# PickupBoard.net
KiCad netlist of a schematic drawn in EAGLE
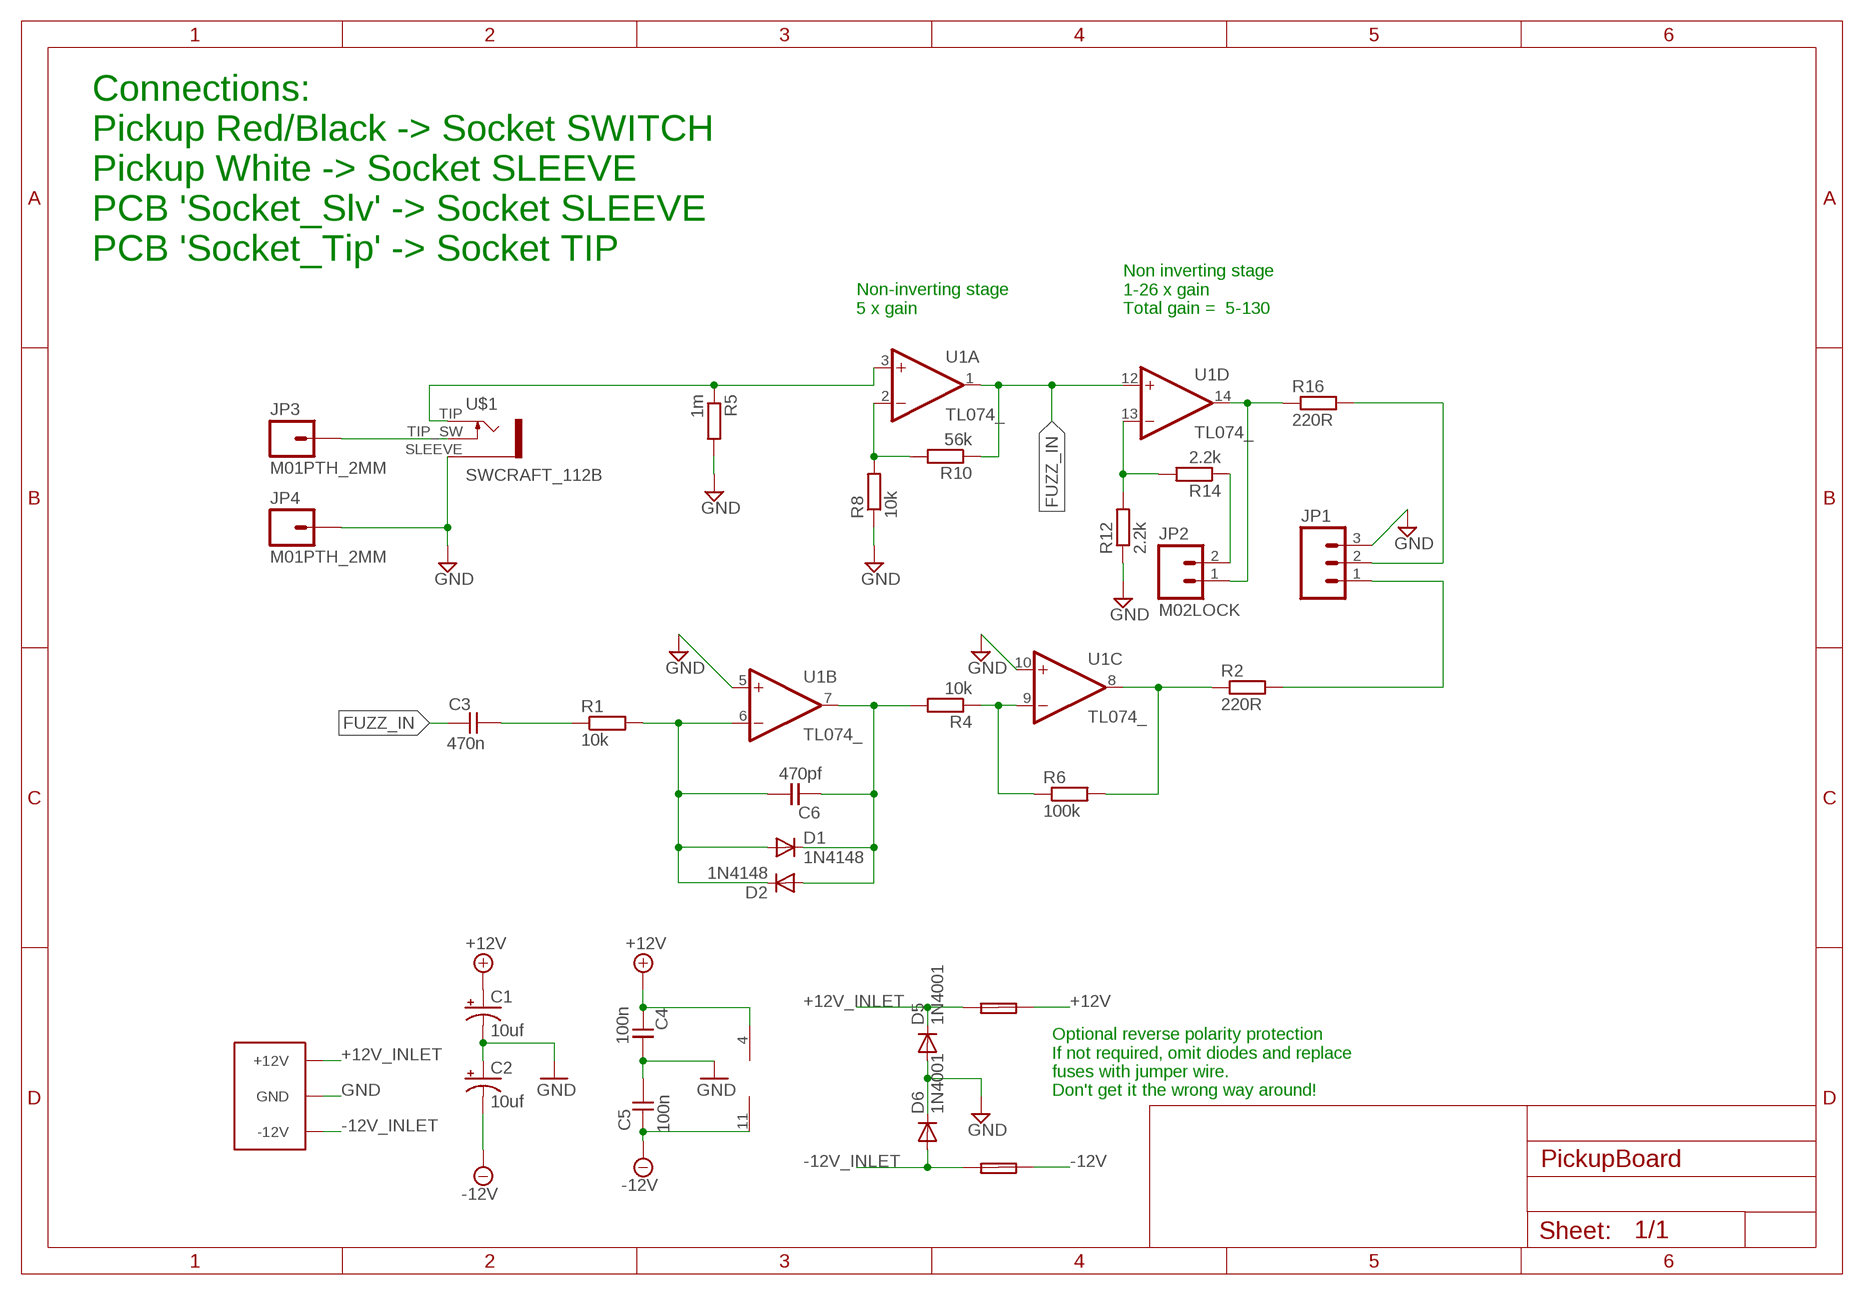
[diagram p0: schematic, sheet 1]

(export (version "E")
  (design (tool "Eeschema 10.0.6"))
  (components
    (comp (ref "1")
      (value "FUSE")
      (footprint "eagle-import:C050H075X075")
      (libsource (lib "eagle-import") (part "PTC_FUSEPOLY_FUSE"))
    )
    (comp (ref "C1")
      (value "10uf")
      (footprint "eagle-import:CPOL-RADIAL-10UF-25V")
      (libsource (lib "eagle-import") (part "CAP_POLPTH2"))
    )
    (comp (ref "C2")
      (value "10uf")
      (footprint "eagle-import:CPOL-RADIAL-10UF-25V")
      (libsource (lib "eagle-import") (part "CAP_POLPTH2"))
    )
    (comp (ref "C3")
      (value "470n")
      (footprint "eagle-import:C050-024X044")
      (libsource (lib "eagle-import") (part "C-EU050-024X044"))
    )
    (comp (ref "C4")
      (value "100n")
      (footprint "eagle-import:C050-024X044")
      (libsource (lib "eagle-import") (part "C-EU050-024X044"))
    )
    (comp (ref "C5")
      (value "100n")
      (footprint "eagle-import:C050-024X044")
      (libsource (lib "eagle-import") (part "C-EU050-024X044"))
    )
    (comp (ref "C6")
      (value "470pf")
      (footprint "eagle-import:C050-024X044")
      (libsource (lib "eagle-import") (part "C-EU050-024X044"))
    )
    (comp (ref "D1")
      (value "1N4148")
      (footprint "eagle-import:DO35-7")
      (libsource (lib "eagle-import") (part "SMALL_DIODEDO35-7"))
    )
    (comp (ref "D2")
      (value "1N4148")
      (footprint "eagle-import:DO35-7")
      (libsource (lib "eagle-import") (part "SMALL_DIODEDO35-7"))
    )
    (comp (ref "D5")
      (value "1N4001")
      (footprint "eagle-import:DO41-10")
      (libsource (lib "eagle-import") (part "1N4004"))
    )
    (comp (ref "D6")
      (value "1N4001")
      (footprint "eagle-import:DO41-10")
      (libsource (lib "eagle-import") (part "1N4004"))
    )
    (comp (ref "FUSE")
      (value "FUSE")
      (footprint "eagle-import:C050H075X075")
      (libsource (lib "eagle-import") (part "PTC_FUSEPOLY_FUSE"))
    )
    (comp (ref "JP1")
      (value "M03LOCK")
      (footprint "eagle-import:1X03_LOCK")
      (libsource (lib "eagle-import") (part "M03LOCK"))
    )
    (comp (ref "JP2")
      (value "M02LOCK")
      (footprint "eagle-import:1X02_LOCK")
      (libsource (lib "eagle-import") (part "M02LOCK"))
    )
    (comp (ref "JP3")
      (value "M01PTH_2MM")
      (footprint "eagle-import:1X01_2MM")
      (libsource (lib "eagle-import") (part "M01PTH_2MM"))
    )
    (comp (ref "JP4")
      (value "M01PTH_2MM")
      (footprint "eagle-import:1X01_2MM")
      (libsource (lib "eagle-import") (part "M01PTH_2MM"))
    )
    (comp (ref "R1")
      (value "10k")
      (footprint "eagle-import:7MM_RESISTOR")
      (libsource (lib "eagle-import") (part "RESISTOR7MM"))
    )
    (comp (ref "R2")
      (value "220R")
      (footprint "eagle-import:7MM_RESISTOR")
      (libsource (lib "eagle-import") (part "RESISTOR7MM"))
    )
    (comp (ref "R4")
      (value "10k")
      (footprint "eagle-import:7MM_RESISTOR")
      (libsource (lib "eagle-import") (part "RESISTOR7MM"))
    )
    (comp (ref "R5")
      (value "1m")
      (footprint "eagle-import:7MM_RESISTOR")
      (libsource (lib "eagle-import") (part "RESISTOR7MM"))
    )
    (comp (ref "R6")
      (value "100k")
      (footprint "eagle-import:7MM_RESISTOR")
      (libsource (lib "eagle-import") (part "RESISTOR7MM"))
    )
    (comp (ref "R8")
      (value "10k")
      (footprint "eagle-import:7MM_RESISTOR")
      (libsource (lib "eagle-import") (part "RESISTOR7MM"))
    )
    (comp (ref "R10")
      (value "56k")
      (footprint "eagle-import:7MM_RESISTOR")
      (libsource (lib "eagle-import") (part "RESISTOR7MM"))
    )
    (comp (ref "R12")
      (value "2.2k")
      (footprint "eagle-import:7MM_RESISTOR")
      (libsource (lib "eagle-import") (part "RESISTOR7MM"))
    )
    (comp (ref "R14")
      (value "2.2k")
      (footprint "eagle-import:7MM_RESISTOR")
      (libsource (lib "eagle-import") (part "RESISTOR7MM"))
    )
    (comp (ref "R16")
      (value "220R")
      (footprint "eagle-import:7MM_RESISTOR")
      (libsource (lib "eagle-import") (part "RESISTOR7MM"))
    )
    (comp (ref "U$1")
      (value "SWCRAFT_112B")
      (footprint "eagle-import:SWCRAFT_112_SLOTS")
      (libsource (lib "eagle-import") (part "SWCRAFT_112B"))
    )
    (comp (ref "U$2")
      (value "EURO_POWER_LOCK")
      (footprint "eagle-import:EURO_PWR_HEADER_LOCK")
      (libsource (lib "eagle-import") (part "EURO_POWER_LOCK"))
    )
    (comp (ref "U1")
      (value "TL074_")
      (footprint "eagle-import:DIL14")
      (libsource (lib "eagle-import") (part "TL074_"))
    )
  )
  (nets
    (net (code "1") (name "+12V") (class "Default")
      (node (ref "1") (pin "2") (pinfunction "P$2_2") (pintype "bidirectional"))
      (node (ref "C1") (pin "1") (pinfunction "+_1") (pintype "passive"))
      (node (ref "C4") (pin "2") (pinfunction "2_2") (pintype "passive"))
      (node (ref "U1") (pin "4") (pinfunction "V+_4") (pintype "power_in"))
    )
    (net (code "2") (name "-12V") (class "Default")
      (node (ref "C2") (pin "2") (pinfunction "-_2") (pintype "passive"))
      (node (ref "C5") (pin "2") (pinfunction "2_2") (pintype "passive"))
      (node (ref "FUSE") (pin "2") (pinfunction "P$2_2") (pintype "bidirectional"))
      (node (ref "U1") (pin "11") (pinfunction "V-_11") (pintype "power_in"))
    )
    (net (code "3") (name "/+12V_INLET") (class "Default")
      (node (ref "1") (pin "1") (pinfunction "P$1_1") (pintype "bidirectional"))
      (node (ref "D5") (pin "C") (pinfunction "C_C") (pintype "passive"))
      (node (ref "U$2") (pin "POS1") (pinfunction "+12V_POS1") (pintype "bidirectional"))
      (node (ref "U$2") (pin "POS2") (pinfunction "+12V_POS2") (pintype "bidirectional"))
    )
    (net (code "4") (name "/-12V_INLET") (class "Default")
      (node (ref "D6") (pin "A") (pinfunction "A_A") (pintype "passive"))
      (node (ref "FUSE") (pin "1") (pinfunction "P$1_1") (pintype "bidirectional"))
      (node (ref "U$2") (pin "NEG1") (pinfunction "-12V_NEG1") (pintype "bidirectional"))
      (node (ref "U$2") (pin "NEG2") (pinfunction "-12V_NEG2") (pintype "bidirectional"))
    )
    (net (code "5") (name "FUZZ_IN") (class "Default")
      (node (ref "C3") (pin "2") (pinfunction "2_2") (pintype "passive"))
      (node (ref "R10") (pin "1") (pinfunction "1_1") (pintype "passive"))
      (node (ref "U1") (pin "1") (pinfunction "OUT_1") (pintype "output"))
      (node (ref "U1") (pin "12") (pinfunction "+IN_12") (pintype "input"))
    )
    (net (code "6") (name "GND") (class "Default")
      (node (ref "C1") (pin "2") (pinfunction "-_2") (pintype "passive"))
      (node (ref "C2") (pin "1") (pinfunction "+_1") (pintype "passive"))
      (node (ref "C4") (pin "1") (pinfunction "1_1") (pintype "passive"))
      (node (ref "C5") (pin "1") (pinfunction "1_1") (pintype "passive"))
      (node (ref "D5") (pin "A") (pinfunction "A_A") (pintype "passive"))
      (node (ref "D6") (pin "C") (pinfunction "C_C") (pintype "passive"))
      (node (ref "JP1") (pin "3") (pinfunction "3_3") (pintype "passive"))
      (node (ref "JP4") (pin "1") (pinfunction "1_1") (pintype "passive"))
      (node (ref "R12") (pin "1") (pinfunction "1_1") (pintype "passive"))
      (node (ref "R5") (pin "2") (pinfunction "2_2") (pintype "passive"))
      (node (ref "R8") (pin "1") (pinfunction "1_1") (pintype "passive"))
      (node (ref "U$1") (pin "SLEEVE") (pinfunction "5_SLEEVE") (pintype "passive"))
      (node (ref "U$2") (pin "GND1") (pinfunction "GND_GND1") (pintype "bidirectional"))
      (node (ref "U$2") (pin "GND2") (pinfunction "GND_GND2") (pintype "bidirectional"))
      (node (ref "U$2") (pin "GND3") (pinfunction "GND_GND3") (pintype "bidirectional"))
      (node (ref "U$2") (pin "GND4") (pinfunction "GND_GND4") (pintype "bidirectional"))
      (node (ref "U$2") (pin "GND5") (pinfunction "GND_GND5") (pintype "bidirectional"))
      (node (ref "U$2") (pin "GND6") (pinfunction "GND_GND6") (pintype "bidirectional"))
      (node (ref "U1") (pin "10") (pinfunction "+IN_10") (pintype "input"))
      (node (ref "U1") (pin "5") (pinfunction "+IN_5") (pintype "input"))
    )
    (net (code "7") (name "Net-(C3-Pad1)") (class "Default")
      (node (ref "C3") (pin "1") (pinfunction "1_1") (pintype "passive"))
      (node (ref "R1") (pin "1") (pinfunction "1_1") (pintype "passive"))
    )
    (net (code "8") (name "Net-(JP1-Pad1)") (class "Default")
      (node (ref "JP1") (pin "1") (pinfunction "1_1") (pintype "passive"))
      (node (ref "R2") (pin "2") (pinfunction "2_2") (pintype "passive"))
    )
    (net (code "9") (name "Net-(JP1-Pad2)") (class "Default")
      (node (ref "JP1") (pin "2") (pinfunction "2_2") (pintype "passive"))
      (node (ref "R16") (pin "2") (pinfunction "2_2") (pintype "passive"))
    )
    (net (code "10") (name "Net-(JP2-Pad2)") (class "Default")
      (node (ref "JP2") (pin "2") (pinfunction "2_2") (pintype "passive"))
      (node (ref "R14") (pin "1") (pinfunction "1_1") (pintype "passive"))
    )
    (net (code "11") (name "Net-(U$1-3)") (class "Default")
      (node (ref "R5") (pin "1") (pinfunction "1_1") (pintype "passive"))
      (node (ref "U$1") (pin "TIP") (pinfunction "3_TIP") (pintype "passive"))
      (node (ref "U1") (pin "3") (pinfunction "+IN_3") (pintype "input"))
    )
    (net (code "12") (name "Net-(U$1-4)") (class "Default")
      (node (ref "JP3") (pin "1") (pinfunction "1_1") (pintype "passive"))
      (node (ref "U$1") (pin "TIP_SW") (pinfunction "4_TIP_SW") (pintype "passive"))
    )
    (net (code "13") (name "Net-(U1A--IN)") (class "Default")
      (node (ref "R10") (pin "2") (pinfunction "2_2") (pintype "passive"))
      (node (ref "R8") (pin "2") (pinfunction "2_2") (pintype "passive"))
      (node (ref "U1") (pin "2") (pinfunction "-IN_2") (pintype "input"))
    )
    (net (code "14") (name "Net-(U1B--IN)") (class "Default")
      (node (ref "C6") (pin "1") (pinfunction "1_1") (pintype "passive"))
      (node (ref "D1") (pin "A") (pinfunction "A_A") (pintype "passive"))
      (node (ref "D2") (pin "C") (pinfunction "C_C") (pintype "passive"))
      (node (ref "R1") (pin "2") (pinfunction "2_2") (pintype "passive"))
      (node (ref "U1") (pin "6") (pinfunction "-IN_6") (pintype "input"))
    )
    (net (code "15") (name "Net-(U1B-OUT)") (class "Default")
      (node (ref "C6") (pin "2") (pinfunction "2_2") (pintype "passive"))
      (node (ref "D1") (pin "C") (pinfunction "C_C") (pintype "passive"))
      (node (ref "D2") (pin "A") (pinfunction "A_A") (pintype "passive"))
      (node (ref "R4") (pin "2") (pinfunction "2_2") (pintype "passive"))
      (node (ref "U1") (pin "7") (pinfunction "OUT_7") (pintype "output"))
    )
    (net (code "16") (name "Net-(U1C--IN)") (class "Default")
      (node (ref "R4") (pin "1") (pinfunction "1_1") (pintype "passive"))
      (node (ref "R6") (pin "1") (pinfunction "1_1") (pintype "passive"))
      (node (ref "U1") (pin "9") (pinfunction "-IN_9") (pintype "input"))
    )
    (net (code "17") (name "Net-(U1C-OUT)") (class "Default")
      (node (ref "R2") (pin "1") (pinfunction "1_1") (pintype "passive"))
      (node (ref "R6") (pin "2") (pinfunction "2_2") (pintype "passive"))
      (node (ref "U1") (pin "8") (pinfunction "OUT_8") (pintype "output"))
    )
    (net (code "18") (name "Net-(U1D--IN)") (class "Default")
      (node (ref "R12") (pin "2") (pinfunction "2_2") (pintype "passive"))
      (node (ref "R14") (pin "2") (pinfunction "2_2") (pintype "passive"))
      (node (ref "U1") (pin "13") (pinfunction "-IN_13") (pintype "input"))
    )
    (net (code "19") (name "Net-(U1D-OUT)") (class "Default")
      (node (ref "JP2") (pin "1") (pinfunction "1_1") (pintype "passive"))
      (node (ref "R16") (pin "1") (pinfunction "1_1") (pintype "passive"))
      (node (ref "U1") (pin "14") (pinfunction "OUT_14") (pintype "output"))
    )
  )
)
